# ENGI301_Project2b.net
KiCad netlist of a schematic drawn in EAGLE
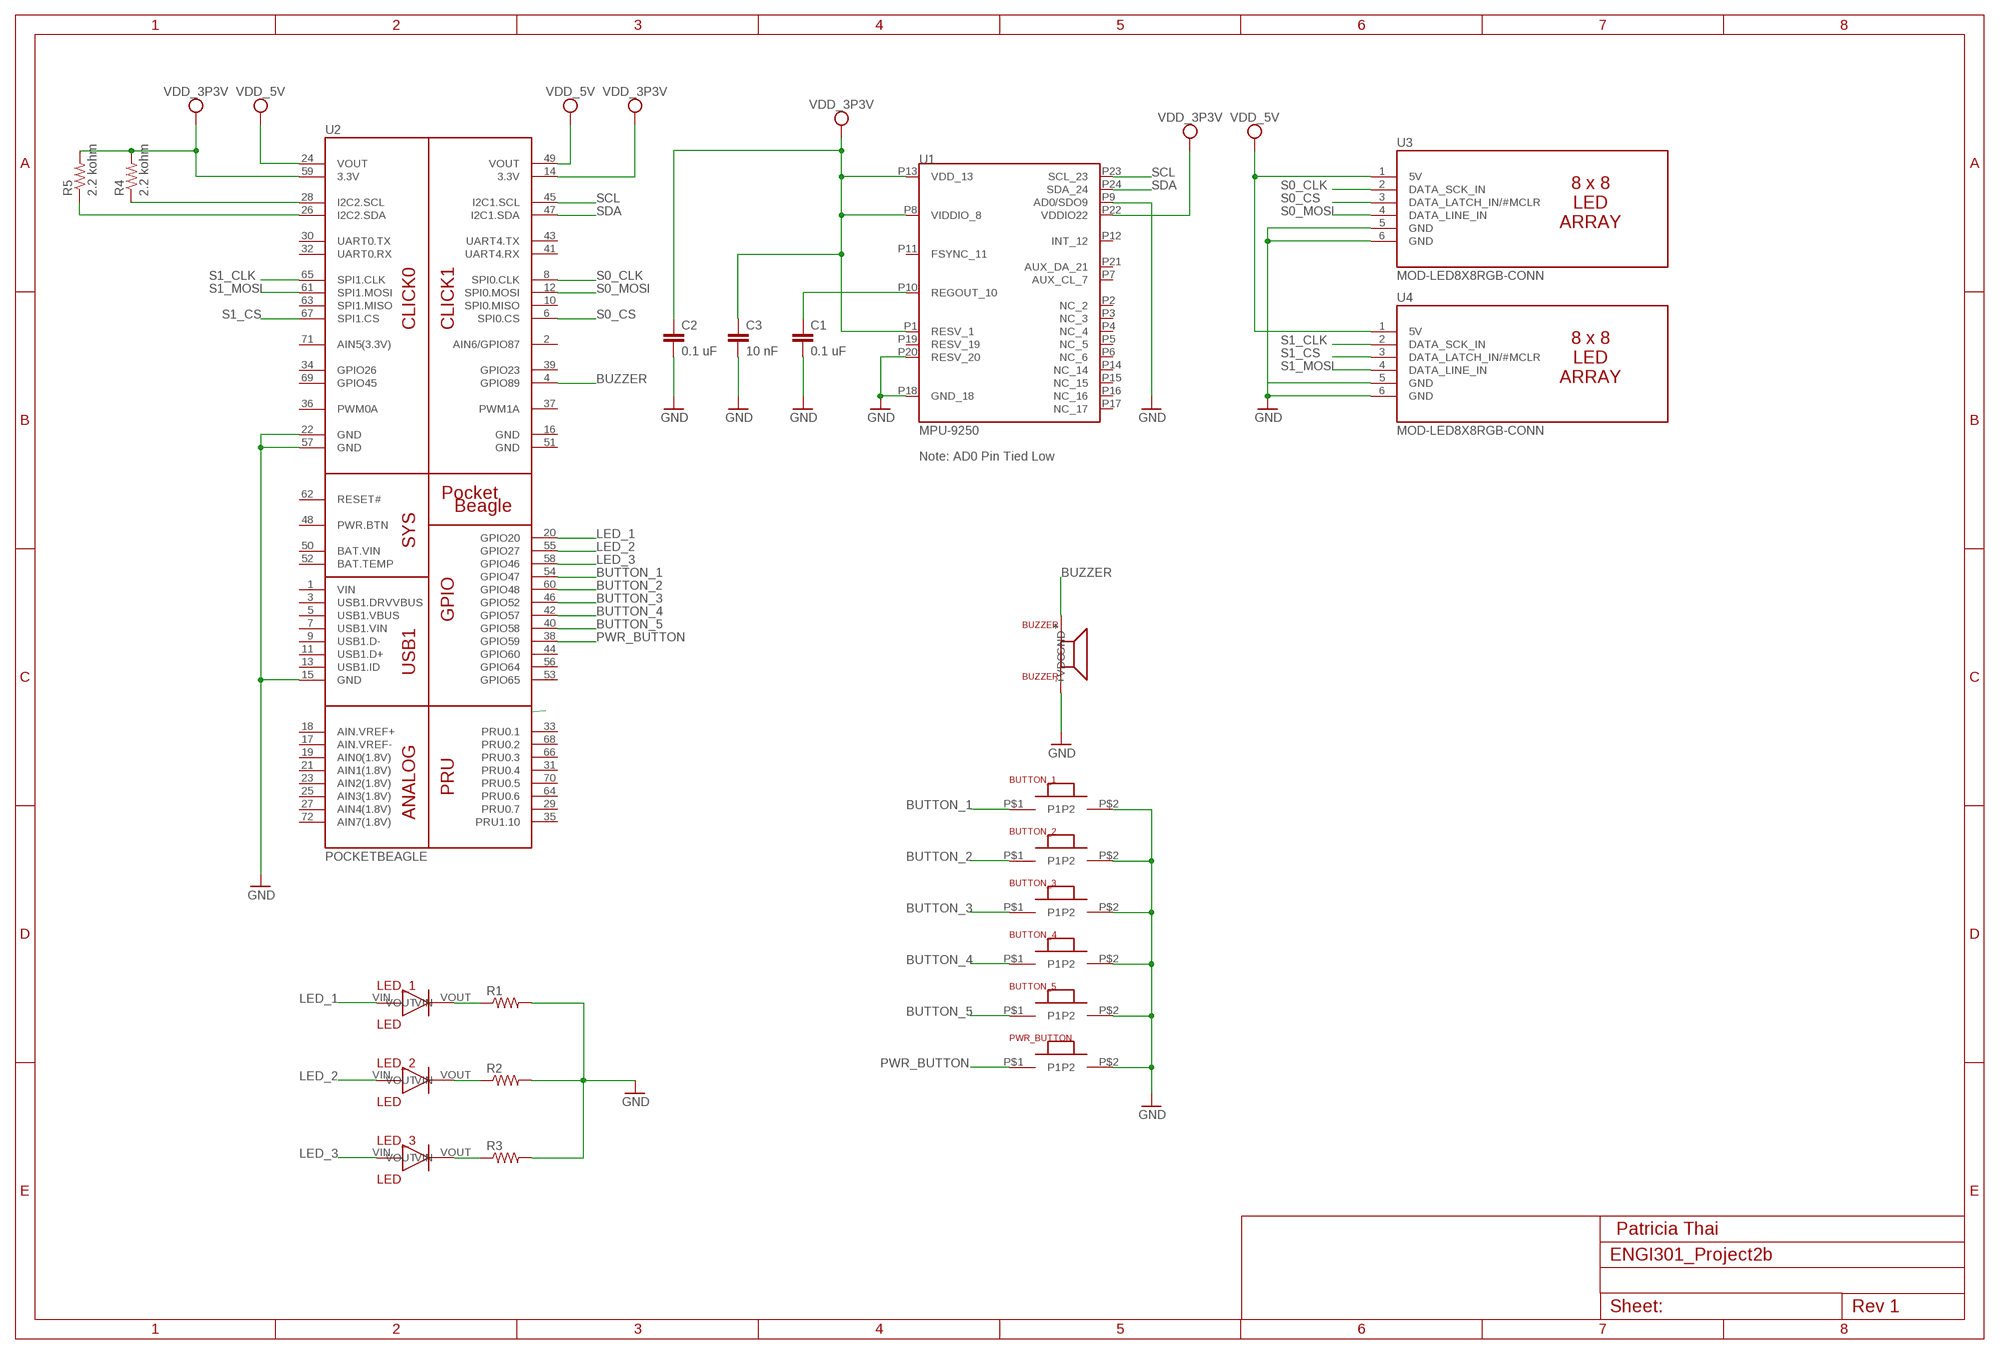
[diagram p0: schematic, sheet 1]

(export (version "E")
  (design (tool "Eeschema 10.0.6"))
  (components
    (comp (ref "BUTTON_1")
      (value "BUTTON")
      (footprint "eagle-import:BUTTON")
      (libsource (lib "eagle-import") (part "BUTTON"))
    )
    (comp (ref "BUTTON_2")
      (value "BUTTON")
      (footprint "eagle-import:BUTTON")
      (libsource (lib "eagle-import") (part "BUTTON"))
    )
    (comp (ref "BUTTON_3")
      (value "BUTTON")
      (footprint "eagle-import:BUTTON")
      (libsource (lib "eagle-import") (part "BUTTON"))
    )
    (comp (ref "BUTTON_4")
      (value "BUTTON")
      (footprint "eagle-import:BUTTON")
      (libsource (lib "eagle-import") (part "BUTTON"))
    )
    (comp (ref "BUTTON_5")
      (value "BUTTON")
      (footprint "eagle-import:BUTTON")
      (libsource (lib "eagle-import") (part "BUTTON"))
    )
    (comp (ref "BUZZER")
      (value "BUZZER")
      (footprint "eagle-import:BUZZER")
      (libsource (lib "eagle-import") (part "BUZZER"))
    )
    (comp (ref "C1")
      (value "0.1 uF")
      (footprint "eagle-import:C0603")
      (libsource (lib "eagle-import") (part "C_C0603"))
    )
    (comp (ref "C2")
      (value "0.1 uF")
      (footprint "eagle-import:C0603")
      (libsource (lib "eagle-import") (part "C_C0603"))
    )
    (comp (ref "C3")
      (value "10 nF")
      (footprint "eagle-import:C0603")
      (libsource (lib "eagle-import") (part "C_C0603"))
    )
    (comp (ref "LED_1")
      (value "LED")
      (footprint "eagle-import:LED")
      (libsource (lib "eagle-import") (part "LED"))
    )
    (comp (ref "LED_2")
      (value "LED")
      (footprint "eagle-import:LED")
      (libsource (lib "eagle-import") (part "LED"))
    )
    (comp (ref "LED_3")
      (value "LED")
      (footprint "eagle-import:LED")
      (libsource (lib "eagle-import") (part "LED"))
    )
    (comp (ref "PWR_BUTTON")
      (value "BUTTON")
      (footprint "eagle-import:BUTTON")
      (libsource (lib "eagle-import") (part "BUTTON"))
    )
    (comp (ref "R1")
      (value "R_R0603")
      (footprint "eagle-import:R0603")
      (libsource (lib "eagle-import") (part "R_R0603"))
    )
    (comp (ref "R2")
      (value "R_R0603")
      (footprint "eagle-import:R0603")
      (libsource (lib "eagle-import") (part "R_R0603"))
    )
    (comp (ref "R3")
      (value "R_R0603")
      (footprint "eagle-import:R0603")
      (libsource (lib "eagle-import") (part "R_R0603"))
    )
    (comp (ref "R4")
      (value "2.2 kohm")
      (footprint "eagle-import:R0603")
      (libsource (lib "eagle-import") (part "ENGI301_design_example_R_R0603"))
    )
    (comp (ref "R5")
      (value "2.2 kohm")
      (footprint "eagle-import:R0603")
      (libsource (lib "eagle-import") (part "ENGI301_design_example_R_R0603"))
    )
    (comp (ref "U1")
      (value "MPU-9250")
      (footprint "eagle-import:MPU-9250")
      (libsource (lib "eagle-import") (part "MPU-9250"))
    )
    (comp (ref "U2")
      (value "POCKETBEAGLE")
      (footprint "eagle-import:POCKETBEAGLE")
      (libsource (lib "eagle-import") (part "POCKETBEAGLE"))
    )
    (comp (ref "U3")
      (value "MOD-LED8X8RGB-CONN")
      (footprint "eagle-import:FE06W")
      (libsource (lib "eagle-import") (part "MOD-LED8X8RGB-CONN"))
    )
    (comp (ref "U4")
      (value "MOD-LED8X8RGB-CONN")
      (footprint "eagle-import:FE06W")
      (libsource (lib "eagle-import") (part "MOD-LED8X8RGB-CONN"))
    )
  )
  (nets
    (net (code "1") (name "/BUTTON_1") (class "Default")
      (node (ref "BUTTON_1") (pin "P$1") (pinfunction "P1_P$1") (pintype "bidirectional"))
      (node (ref "U2") (pin "54") (pinfunction "GPIO47_54") (pintype "bidirectional"))
    )
    (net (code "2") (name "/BUTTON_2") (class "Default")
      (node (ref "BUTTON_2") (pin "P$1") (pinfunction "P1_P$1") (pintype "bidirectional"))
      (node (ref "U2") (pin "60") (pinfunction "GPIO48_60") (pintype "bidirectional"))
    )
    (net (code "3") (name "/BUTTON_3") (class "Default")
      (node (ref "BUTTON_3") (pin "P$1") (pinfunction "P1_P$1") (pintype "bidirectional"))
      (node (ref "U2") (pin "46") (pinfunction "GPIO52_46") (pintype "bidirectional"))
    )
    (net (code "4") (name "/BUTTON_4") (class "Default")
      (node (ref "BUTTON_4") (pin "P$1") (pinfunction "P1_P$1") (pintype "bidirectional"))
      (node (ref "U2") (pin "42") (pinfunction "GPIO57_42") (pintype "bidirectional"))
    )
    (net (code "5") (name "/BUTTON_5") (class "Default")
      (node (ref "BUTTON_5") (pin "P$1") (pinfunction "P1_P$1") (pintype "bidirectional"))
      (node (ref "U2") (pin "40") (pinfunction "GPIO58_40") (pintype "bidirectional"))
    )
    (net (code "6") (name "/BUZZER") (class "Default")
      (node (ref "BUZZER") (pin "+") (pinfunction "+VDC_+") (pintype "bidirectional"))
      (node (ref "U2") (pin "4") (pinfunction "GPIO89_4") (pintype "bidirectional"))
    )
    (net (code "7") (name "/LED_1") (class "Default")
      (node (ref "LED_1") (pin "VIN") (pinfunction "VIN_VIN") (pintype "bidirectional"))
      (node (ref "U2") (pin "20") (pinfunction "GPIO20_20") (pintype "bidirectional"))
    )
    (net (code "8") (name "/LED_2") (class "Default")
      (node (ref "LED_2") (pin "VIN") (pinfunction "VIN_VIN") (pintype "bidirectional"))
      (node (ref "U2") (pin "55") (pinfunction "GPIO27_55") (pintype "bidirectional"))
    )
    (net (code "9") (name "/LED_3") (class "Default")
      (node (ref "LED_3") (pin "VIN") (pinfunction "VIN_VIN") (pintype "bidirectional"))
      (node (ref "U2") (pin "58") (pinfunction "GPIO46_58") (pintype "bidirectional"))
    )
    (net (code "10") (name "/PWR_BUTTON") (class "Default")
      (node (ref "PWR_BUTTON") (pin "P$1") (pinfunction "P1_P$1") (pintype "bidirectional"))
      (node (ref "U2") (pin "38") (pinfunction "GPIO59_38") (pintype "bidirectional"))
    )
    (net (code "11") (name "/S0_CLK") (class "Default")
      (node (ref "U2") (pin "8") (pinfunction "SPI0.CLK_8") (pintype "bidirectional"))
      (node (ref "U3") (pin "2") (pinfunction "DATA_SCK_IN_2") (pintype "bidirectional"))
    )
    (net (code "12") (name "/S0_CS") (class "Default")
      (node (ref "U2") (pin "6") (pinfunction "SPI0.CS_6") (pintype "bidirectional"))
      (node (ref "U3") (pin "3") (pinfunction "DATA_LATCH_IN/#MCLR_3") (pintype "bidirectional"))
    )
    (net (code "13") (name "/S0_MOSI") (class "Default")
      (node (ref "U2") (pin "12") (pinfunction "SPI0.MOSI_12") (pintype "bidirectional"))
      (node (ref "U3") (pin "4") (pinfunction "DATA_LINE_IN_4") (pintype "bidirectional"))
    )
    (net (code "14") (name "/S1_CLK") (class "Default")
      (node (ref "U2") (pin "65") (pinfunction "SPI1.CLK_65") (pintype "bidirectional"))
      (node (ref "U4") (pin "2") (pinfunction "DATA_SCK_IN_2") (pintype "bidirectional"))
    )
    (net (code "15") (name "/S1_CS") (class "Default")
      (node (ref "U2") (pin "67") (pinfunction "SPI1.CS_67") (pintype "bidirectional"))
      (node (ref "U4") (pin "3") (pinfunction "DATA_LATCH_IN/#MCLR_3") (pintype "bidirectional"))
    )
    (net (code "16") (name "/S1_MOSI") (class "Default")
      (node (ref "U2") (pin "61") (pinfunction "SPI1.MOSI_61") (pintype "bidirectional"))
      (node (ref "U4") (pin "4") (pinfunction "DATA_LINE_IN_4") (pintype "bidirectional"))
    )
    (net (code "17") (name "/SCL") (class "Default")
      (node (ref "U1") (pin "P23") (pinfunction "SCL_23_P23") (pintype "bidirectional"))
      (node (ref "U2") (pin "45") (pinfunction "I2C1.SCL_45") (pintype "bidirectional"))
    )
    (net (code "18") (name "/SDA") (class "Default")
      (node (ref "U1") (pin "P24") (pinfunction "SDA_24_P24") (pintype "bidirectional"))
      (node (ref "U2") (pin "47") (pinfunction "I2C1.SDA_47") (pintype "bidirectional"))
    )
    (net (code "19") (name "GND") (class "Default")
      (node (ref "BUTTON_1") (pin "P$2") (pinfunction "P2_P$2") (pintype "bidirectional"))
      (node (ref "BUTTON_2") (pin "P$2") (pinfunction "P2_P$2") (pintype "bidirectional"))
      (node (ref "BUTTON_3") (pin "P$2") (pinfunction "P2_P$2") (pintype "bidirectional"))
      (node (ref "BUTTON_4") (pin "P$2") (pinfunction "P2_P$2") (pintype "bidirectional"))
      (node (ref "BUTTON_5") (pin "P$2") (pinfunction "P2_P$2") (pintype "bidirectional"))
      (node (ref "BUZZER") (pin "-") (pinfunction "GND_-") (pintype "bidirectional"))
      (node (ref "C1") (pin "2") (pinfunction "2_2") (pintype "passive"))
      (node (ref "C2") (pin "2") (pinfunction "2_2") (pintype "passive"))
      (node (ref "C3") (pin "2") (pinfunction "2_2") (pintype "passive"))
      (node (ref "PWR_BUTTON") (pin "P$2") (pinfunction "P2_P$2") (pintype "bidirectional"))
      (node (ref "R1") (pin "2") (pinfunction "2_2") (pintype "passive"))
      (node (ref "R2") (pin "2") (pinfunction "2_2") (pintype "passive"))
      (node (ref "R3") (pin "2") (pinfunction "2_2") (pintype "passive"))
      (node (ref "U1") (pin "P18") (pinfunction "GND_18_P18") (pintype "bidirectional"))
      (node (ref "U1") (pin "P20") (pinfunction "RESV_20_P20") (pintype "bidirectional"))
      (node (ref "U1") (pin "P9") (pinfunction "AD0/SDO9_P9") (pintype "bidirectional"))
      (node (ref "U2") (pin "15") (pinfunction "GND_15") (pintype "bidirectional"))
      (node (ref "U2") (pin "22") (pinfunction "GND_22") (pintype "bidirectional"))
      (node (ref "U2") (pin "57") (pinfunction "GND_57") (pintype "bidirectional"))
      (node (ref "U3") (pin "5") (pinfunction "GND_5") (pintype "bidirectional"))
      (node (ref "U3") (pin "6") (pinfunction "GND_6") (pintype "bidirectional"))
      (node (ref "U4") (pin "5") (pinfunction "GND_5") (pintype "bidirectional"))
      (node (ref "U4") (pin "6") (pinfunction "GND_6") (pintype "bidirectional"))
    )
    (net (code "20") (name "Net-(LED_1-PadVOUT)") (class "Default")
      (node (ref "LED_1") (pin "VOUT") (pinfunction "VOUT_VOUT") (pintype "bidirectional"))
      (node (ref "R1") (pin "1") (pinfunction "1_1") (pintype "passive"))
    )
    (net (code "21") (name "Net-(LED_2-PadVOUT)") (class "Default")
      (node (ref "LED_2") (pin "VOUT") (pinfunction "VOUT_VOUT") (pintype "bidirectional"))
      (node (ref "R2") (pin "1") (pinfunction "1_1") (pintype "passive"))
    )
    (net (code "22") (name "Net-(LED_3-PadVOUT)") (class "Default")
      (node (ref "LED_3") (pin "VOUT") (pinfunction "VOUT_VOUT") (pintype "bidirectional"))
      (node (ref "R3") (pin "1") (pinfunction "1_1") (pintype "passive"))
    )
    (net (code "23") (name "Net-(U1-REGOUT_10)") (class "Default")
      (node (ref "C1") (pin "1") (pinfunction "1_1") (pintype "passive"))
      (node (ref "U1") (pin "P10") (pinfunction "REGOUT_10_P10") (pintype "bidirectional"))
    )
    (net (code "24") (name "Net-(U2-I2C2.SCL)") (class "Default")
      (node (ref "R4") (pin "1") (pinfunction "1_1") (pintype "passive"))
      (node (ref "U2") (pin "28") (pinfunction "I2C2.SCL_28") (pintype "bidirectional"))
    )
    (net (code "25") (name "Net-(U2-I2C2.SDA)") (class "Default")
      (node (ref "R5") (pin "1") (pinfunction "1_1") (pintype "passive"))
      (node (ref "U2") (pin "26") (pinfunction "I2C2.SDA_26") (pintype "bidirectional"))
    )
    (net (code "26") (name "VDD_3P3V") (class "Default")
      (node (ref "C2") (pin "1") (pinfunction "1_1") (pintype "passive"))
      (node (ref "C3") (pin "1") (pinfunction "1_1") (pintype "passive"))
      (node (ref "R4") (pin "2") (pinfunction "2_2") (pintype "passive"))
      (node (ref "R5") (pin "2") (pinfunction "2_2") (pintype "passive"))
      (node (ref "U1") (pin "P1") (pinfunction "RESV_1_P1") (pintype "bidirectional"))
      (node (ref "U1") (pin "P13") (pinfunction "VDD_13_P13") (pintype "bidirectional"))
      (node (ref "U1") (pin "P22") (pinfunction "VDDIO22_P22") (pintype "bidirectional"))
      (node (ref "U1") (pin "P8") (pinfunction "VIDDIO_8_P8") (pintype "bidirectional"))
      (node (ref "U2") (pin "14") (pinfunction "3.3V_14") (pintype "bidirectional"))
      (node (ref "U2") (pin "24") (pinfunction "VOUT_24") (pintype "bidirectional"))
      (node (ref "U2") (pin "49") (pinfunction "VOUT_49") (pintype "bidirectional"))
      (node (ref "U2") (pin "59") (pinfunction "3.3V_59") (pintype "bidirectional"))
      (node (ref "U3") (pin "1") (pinfunction "5V_1") (pintype "bidirectional"))
      (node (ref "U4") (pin "1") (pinfunction "5V_1") (pintype "bidirectional"))
    )
    (net (code "27") (name "unconnected-(U1-AUX_CL_7-PadP7)") (class "Default")
      (node (ref "U1") (pin "P7") (pinfunction "AUX_CL_7_P7") (pintype "bidirectional"))
    )
    (net (code "28") (name "unconnected-(U1-AUX_DA_21-PadP21)") (class "Default")
      (node (ref "U1") (pin "P21") (pinfunction "AUX_DA_21_P21") (pintype "bidirectional"))
    )
    (net (code "29") (name "unconnected-(U1-FSYNC_11-PadP11)") (class "Default")
      (node (ref "U1") (pin "P11") (pinfunction "FSYNC_11_P11") (pintype "bidirectional"))
    )
    (net (code "30") (name "unconnected-(U1-INT_12-PadP12)") (class "Default")
      (node (ref "U1") (pin "P12") (pinfunction "INT_12_P12") (pintype "bidirectional"))
    )
    (net (code "31") (name "unconnected-(U1-NC_2-PadP2)") (class "Default")
      (node (ref "U1") (pin "P2") (pinfunction "NC_2_P2") (pintype "bidirectional"))
    )
    (net (code "32") (name "unconnected-(U1-NC_3-PadP3)") (class "Default")
      (node (ref "U1") (pin "P3") (pinfunction "NC_3_P3") (pintype "bidirectional"))
    )
    (net (code "33") (name "unconnected-(U1-NC_4-PadP4)") (class "Default")
      (node (ref "U1") (pin "P4") (pinfunction "NC_4_P4") (pintype "bidirectional"))
    )
    (net (code "34") (name "unconnected-(U1-NC_5-PadP5)") (class "Default")
      (node (ref "U1") (pin "P5") (pinfunction "NC_5_P5") (pintype "bidirectional"))
    )
    (net (code "35") (name "unconnected-(U1-NC_6-PadP6)") (class "Default")
      (node (ref "U1") (pin "P6") (pinfunction "NC_6_P6") (pintype "bidirectional"))
    )
    (net (code "36") (name "unconnected-(U1-NC_14-PadP14)") (class "Default")
      (node (ref "U1") (pin "P14") (pinfunction "NC_14_P14") (pintype "bidirectional"))
    )
    (net (code "37") (name "unconnected-(U1-NC_15-PadP15)") (class "Default")
      (node (ref "U1") (pin "P15") (pinfunction "NC_15_P15") (pintype "bidirectional"))
    )
    (net (code "38") (name "unconnected-(U1-NC_16-PadP16)") (class "Default")
      (node (ref "U1") (pin "P16") (pinfunction "NC_16_P16") (pintype "bidirectional"))
    )
    (net (code "39") (name "unconnected-(U1-NC_17-PadP17)") (class "Default")
      (node (ref "U1") (pin "P17") (pinfunction "NC_17_P17") (pintype "bidirectional"))
    )
    (net (code "40") (name "unconnected-(U1-RESV_19-PadP19)") (class "Default")
      (node (ref "U1") (pin "P19") (pinfunction "RESV_19_P19") (pintype "bidirectional"))
    )
    (net (code "41") (name "unconnected-(U2-AIN.VREF+-Pad18)") (class "Default")
      (node (ref "U2") (pin "18") (pinfunction "AIN.VREF+_18") (pintype "bidirectional"))
    )
    (net (code "42") (name "unconnected-(U2-AIN.VREF--Pad17)") (class "Default")
      (node (ref "U2") (pin "17") (pinfunction "AIN.VREF-_17") (pintype "bidirectional"))
    )
    (net (code "43") (name "unconnected-(U2-AIN0(1.8V)-Pad19)") (class "Default")
      (node (ref "U2") (pin "19") (pinfunction "AIN0(1.8V)_19") (pintype "bidirectional"))
    )
    (net (code "44") (name "unconnected-(U2-AIN1(1.8V)-Pad21)") (class "Default")
      (node (ref "U2") (pin "21") (pinfunction "AIN1(1.8V)_21") (pintype "bidirectional"))
    )
    (net (code "45") (name "unconnected-(U2-AIN2(1.8V)-Pad23)") (class "Default")
      (node (ref "U2") (pin "23") (pinfunction "AIN2(1.8V)_23") (pintype "bidirectional"))
    )
    (net (code "46") (name "unconnected-(U2-AIN3(1.8V)-Pad25)") (class "Default")
      (node (ref "U2") (pin "25") (pinfunction "AIN3(1.8V)_25") (pintype "bidirectional"))
    )
    (net (code "47") (name "unconnected-(U2-AIN4(1.8V)-Pad27)") (class "Default")
      (node (ref "U2") (pin "27") (pinfunction "AIN4(1.8V)_27") (pintype "bidirectional"))
    )
    (net (code "48") (name "unconnected-(U2-AIN5(3.3V)-Pad71)") (class "Default")
      (node (ref "U2") (pin "71") (pinfunction "AIN5(3.3V)_71") (pintype "bidirectional"))
    )
    (net (code "49") (name "unconnected-(U2-AIN6{slash}GPIO87-Pad2)") (class "Default")
      (node (ref "U2") (pin "2") (pinfunction "AIN6/GPIO87_2") (pintype "bidirectional"))
    )
    (net (code "50") (name "unconnected-(U2-AIN7(1.8V)-Pad72)") (class "Default")
      (node (ref "U2") (pin "72") (pinfunction "AIN7(1.8V)_72") (pintype "bidirectional"))
    )
    (net (code "51") (name "unconnected-(U2-BAT.TEMP-Pad52)") (class "Default")
      (node (ref "U2") (pin "52") (pinfunction "BAT.TEMP_52") (pintype "bidirectional"))
    )
    (net (code "52") (name "unconnected-(U2-BAT.VIN-Pad50)") (class "Default")
      (node (ref "U2") (pin "50") (pinfunction "BAT.VIN_50") (pintype "bidirectional"))
    )
    (net (code "53") (name "unconnected-(U2-GND-Pad16)") (class "Default")
      (node (ref "U2") (pin "16") (pinfunction "GND_16") (pintype "bidirectional"))
    )
    (net (code "54") (name "unconnected-(U2-GND-Pad51)") (class "Default")
      (node (ref "U2") (pin "51") (pinfunction "GND_51") (pintype "bidirectional"))
    )
    (net (code "55") (name "unconnected-(U2-GPIO23-Pad39)") (class "Default")
      (node (ref "U2") (pin "39") (pinfunction "GPIO23_39") (pintype "bidirectional"))
    )
    (net (code "56") (name "unconnected-(U2-GPIO26-Pad34)") (class "Default")
      (node (ref "U2") (pin "34") (pinfunction "GPIO26_34") (pintype "bidirectional"))
    )
    (net (code "57") (name "unconnected-(U2-GPIO45-Pad69)") (class "Default")
      (node (ref "U2") (pin "69") (pinfunction "GPIO45_69") (pintype "bidirectional"))
    )
    (net (code "58") (name "unconnected-(U2-GPIO60-Pad44)") (class "Default")
      (node (ref "U2") (pin "44") (pinfunction "GPIO60_44") (pintype "bidirectional"))
    )
    (net (code "59") (name "unconnected-(U2-GPIO64-Pad56)") (class "Default")
      (node (ref "U2") (pin "56") (pinfunction "GPIO64_56") (pintype "bidirectional"))
    )
    (net (code "60") (name "unconnected-(U2-GPIO65-Pad53)") (class "Default")
      (node (ref "U2") (pin "53") (pinfunction "GPIO65_53") (pintype "bidirectional"))
    )
    (net (code "61") (name "unconnected-(U2-PRU0.1-Pad33)") (class "Default")
      (node (ref "U2") (pin "33") (pinfunction "PRU0.1_33") (pintype "bidirectional"))
    )
    (net (code "62") (name "unconnected-(U2-PRU0.2-Pad68)") (class "Default")
      (node (ref "U2") (pin "68") (pinfunction "PRU0.2_68") (pintype "bidirectional"))
    )
    (net (code "63") (name "unconnected-(U2-PRU0.3-Pad66)") (class "Default")
      (node (ref "U2") (pin "66") (pinfunction "PRU0.3_66") (pintype "bidirectional"))
    )
    (net (code "64") (name "unconnected-(U2-PRU0.4-Pad31)") (class "Default")
      (node (ref "U2") (pin "31") (pinfunction "PRU0.4_31") (pintype "bidirectional"))
    )
    (net (code "65") (name "unconnected-(U2-PRU0.5-Pad70)") (class "Default")
      (node (ref "U2") (pin "70") (pinfunction "PRU0.5_70") (pintype "bidirectional"))
    )
    (net (code "66") (name "unconnected-(U2-PRU0.6-Pad64)") (class "Default")
      (node (ref "U2") (pin "64") (pinfunction "PRU0.6_64") (pintype "bidirectional"))
    )
    (net (code "67") (name "unconnected-(U2-PRU0.7-Pad29)") (class "Default")
      (node (ref "U2") (pin "29") (pinfunction "PRU0.7_29") (pintype "bidirectional"))
    )
    (net (code "68") (name "unconnected-(U2-PRU1.10-Pad35)") (class "Default")
      (node (ref "U2") (pin "35") (pinfunction "PRU1.10_35") (pintype "bidirectional"))
    )
    (net (code "69") (name "unconnected-(U2-PWM0A-Pad36)") (class "Default")
      (node (ref "U2") (pin "36") (pinfunction "PWM0A_36") (pintype "bidirectional"))
    )
    (net (code "70") (name "unconnected-(U2-PWM1A-Pad37)") (class "Default")
      (node (ref "U2") (pin "37") (pinfunction "PWM1A_37") (pintype "bidirectional"))
    )
    (net (code "71") (name "unconnected-(U2-PWR.BTN-Pad48)") (class "Default")
      (node (ref "U2") (pin "48") (pinfunction "PWR.BTN_48") (pintype "bidirectional"))
    )
    (net (code "72") (name "unconnected-(U2-RESET#-Pad62)") (class "Default")
      (node (ref "U2") (pin "62") (pinfunction "RESET#_62") (pintype "bidirectional"))
    )
    (net (code "73") (name "unconnected-(U2-SPI0.MISO-Pad10)") (class "Default")
      (node (ref "U2") (pin "10") (pinfunction "SPI0.MISO_10") (pintype "bidirectional"))
    )
    (net (code "74") (name "unconnected-(U2-SPI1.MISO-Pad63)") (class "Default")
      (node (ref "U2") (pin "63") (pinfunction "SPI1.MISO_63") (pintype "bidirectional"))
    )
    (net (code "75") (name "unconnected-(U2-UART0.RX-Pad32)") (class "Default")
      (node (ref "U2") (pin "32") (pinfunction "UART0.RX_32") (pintype "bidirectional"))
    )
    (net (code "76") (name "unconnected-(U2-UART0.TX-Pad30)") (class "Default")
      (node (ref "U2") (pin "30") (pinfunction "UART0.TX_30") (pintype "bidirectional"))
    )
    (net (code "77") (name "unconnected-(U2-UART4.RX-Pad41)") (class "Default")
      (node (ref "U2") (pin "41") (pinfunction "UART4.RX_41") (pintype "bidirectional"))
    )
    (net (code "78") (name "unconnected-(U2-UART4.TX-Pad43)") (class "Default")
      (node (ref "U2") (pin "43") (pinfunction "UART4.TX_43") (pintype "bidirectional"))
    )
    (net (code "79") (name "unconnected-(U2-USB1.D+-Pad11)") (class "Default")
      (node (ref "U2") (pin "11") (pinfunction "USB1.D+_11") (pintype "bidirectional"))
    )
    (net (code "80") (name "unconnected-(U2-USB1.D--Pad9)") (class "Default")
      (node (ref "U2") (pin "9") (pinfunction "USB1.D-_9") (pintype "bidirectional"))
    )
    (net (code "81") (name "unconnected-(U2-USB1.DRVVBUS-Pad3)") (class "Default")
      (node (ref "U2") (pin "3") (pinfunction "USB1.DRVVBUS_3") (pintype "bidirectional"))
    )
    (net (code "82") (name "unconnected-(U2-USB1.ID-Pad13)") (class "Default")
      (node (ref "U2") (pin "13") (pinfunction "USB1.ID_13") (pintype "bidirectional"))
    )
    (net (code "83") (name "unconnected-(U2-USB1.VBUS-Pad5)") (class "Default")
      (node (ref "U2") (pin "5") (pinfunction "USB1.VBUS_5") (pintype "bidirectional"))
    )
    (net (code "84") (name "unconnected-(U2-USB1.VIN-Pad7)") (class "Default")
      (node (ref "U2") (pin "7") (pinfunction "USB1.VIN_7") (pintype "bidirectional"))
    )
    (net (code "85") (name "unconnected-(U2-VIN-Pad1)") (class "Default")
      (node (ref "U2") (pin "1") (pinfunction "VIN_1") (pintype "bidirectional"))
    )
  )
)
